# v009_schematics.net
KiCad netlist of a schematic drawn in Altium Designer
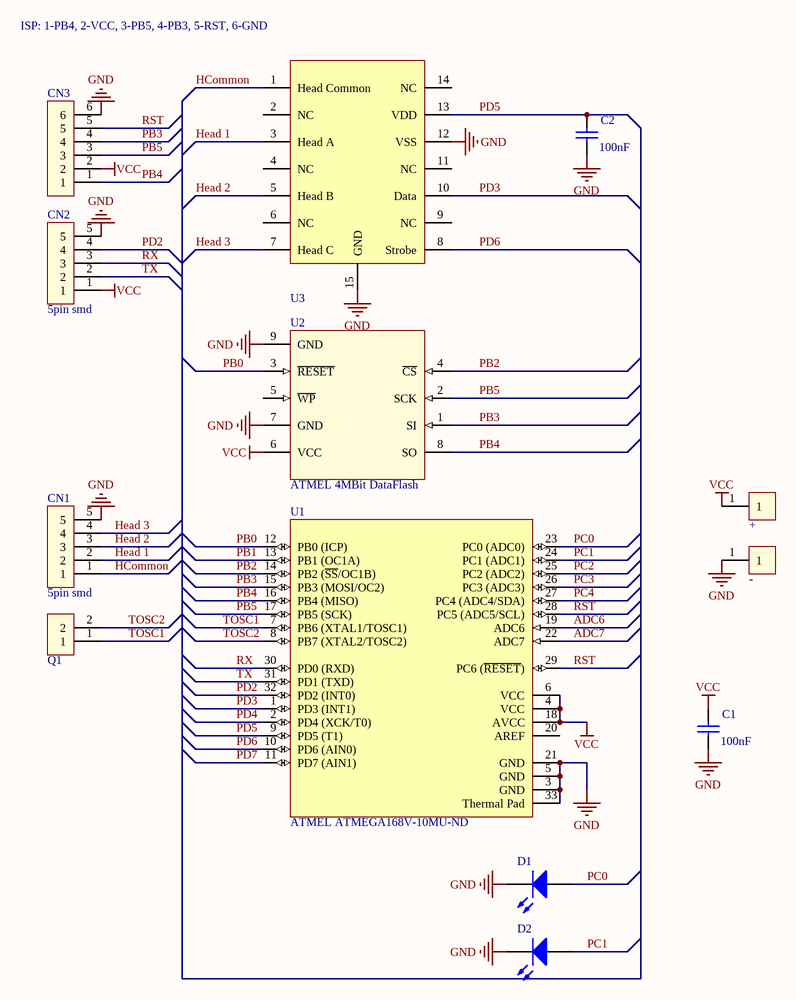
[diagram p0: v009 schematics.SCHDOC]

(export (version "E")
  (design (tool "Eeschema 10.0.6"))
  (components
    (comp (ref "+")
      (value "No component mounted")
      (footprint "SU01LS")
      (libsource (lib "*") (part "1pin smd"))
    )
    (comp (ref "-")
      (value "No component mounted")
      (footprint "SU01LS")
      (libsource (lib "*") (part "1pin smd"))
    )
    (comp (ref "C1")
      (value "100nF")
      (footprint "CC0603(0201)")
      (description "100nf Capacitor - Footprint CC0603 (0201)")
      (fields
        (field (name "DIGI-KEY PART NUMBER") "490-3167-1-ND")
        (field (name "MANUFACTURER") "Murata Electronics")
        (field (name "PUBLISHER") "Altium Limited")
      )
      (libsource (lib "Miscellaneous Devices") (part "Cap"))
    )
    (comp (ref "C2")
      (value "100nF")
      (footprint "CC0603(0201)")
      (description "CAP CER .1UF 6.3V X5R 0201")
      (fields
        (field (name "DIGI-KEY PART NUMBER") "490-3167-1-ND")
        (field (name "PUBLISHER") "Altium Limited")
      )
      (libsource (lib "Miscellaneous Devices") (part "Cap"))
    )
    (comp (ref "CN1")
      (value "5pin smd")
      (footprint "SU05LSR wide")
      (description "No component mounted")
      (libsource (lib "v4lib") (part "5pin smd"))
    )
    (comp (ref "CN2")
      (value "5pin smd")
      (footprint "SU05LSR wide")
      (description "No component mounted")
      (libsource (lib "v4lib") (part "5pin smd"))
    )
    (comp (ref "CN3")
      (value "No component mounted")
      (footprint "SU06LST FULL")
      (libsource (lib "v4lib") (part "6pin smd"))
    )
    (comp (ref "D1")
      (value "LED1")
      (footprint "CC1005(0402)")
      (description "LED 0402 GREEN 465NM TRANSPARENT")
      (fields
        (field (name "DIGI-KEY PART NUMBER") "511-1615-1-ND")
        (field (name "MANUFACTURER") "Rohm Semiconductor")
        (field (name "PUBLISHER") "Altium Limited")
      )
      (libsource (lib "Miscellaneous Devices") (part "LED3"))
    )
    (comp (ref "D2")
      (value "LED1")
      (footprint "CC1005(0402)")
      (description "LED 0402 RED 465NM TRANSPARENT")
      (fields
        (field (name "DIGI-KEY PART NUMBER") "511-1615-1-ND")
        (field (name "MANUFACTURER") "Rohm Semiconductor")
        (field (name "PUBLISHER") "Altium Limited")
      )
      (libsource (lib "Miscellaneous Devices") (part "LED3"))
    )
    (comp (ref "Q1")
      (value "32.768khz crystal 1.5 x 3.2mm")
      (footprint "Quartz SMD (small)")
      (description "CRYSTAL 32.768KHZ 1.5 x 3.2mm")
      (fields
        (field (name "DIGI-KEY PART NUMBER") "535-9542-1-ND")
        (field (name "MANUFACTURER") "Abracon Corporation")
      )
      (libsource (lib "v4lib") (part "2pin smd"))
    )
    (comp (ref "U1")
      (value "ATMEL ATMEGA168V-10MU-ND")
      (footprint "32M1-A L 3")
      (description "ATMEL ATMEGA168V-10MU")
      (fields
        (field (name "DIGI-KEY PART NUMBER") "ATMEGA168V-10MU-ND")
        (field (name "MANUFACTURER") "ATMEL")
        (field (name "PUBLISHER") "Altium Limited")
      )
      (libsource (lib "Atmel Microcontroller 8-Bit AVR") (part "ATmega8L-8MC"))
    )
    (comp (ref "U2")
      (value "ATMEL 4MBit DataFlash")
      (footprint "8m1-a mlf 3")
      (libsource (lib "v4lib") (part "at45db041b"))
    )
    (comp (ref "U3")
      (value "Asic 3V MLF14")
      (footprint "delta asic - 5")
      (fields (field (name "MANUFACTURER") "Magtek") (field (name "MANUFACTURER PART NUMBER") "21006540"))
      (libsource (lib "v4lib") (part "delta asic 3volt"))
    )
  )
  (nets
    (net (code "1") (name "/ADC6") (class "Default")
      (node (ref "U1") (pin "19") (pinfunction "ADC6_19") (pintype "input"))
    )
    (net (code "2") (name "/ADC7") (class "Default")
      (node (ref "U1") (pin "22") (pinfunction "ADC7_22") (pintype "input"))
    )
    (net (code "3") (name "/HCommon") (class "Default")
      (node (ref "CN1") (pin "1") (pinfunction "1_1") (pintype "passive"))
      (node (ref "U3") (pin "1") (pinfunction "Head_Common_1") (pintype "passive"))
    )
    (net (code "4") (name "/Head 1") (class "Default")
      (node (ref "CN1") (pin "2") (pinfunction "2_2") (pintype "passive"))
      (node (ref "U3") (pin "3") (pinfunction "Head_A_3") (pintype "passive"))
    )
    (net (code "5") (name "/Head 2") (class "Default")
      (node (ref "CN1") (pin "3") (pinfunction "3_3") (pintype "passive"))
      (node (ref "U3") (pin "5") (pinfunction "Head_B_5") (pintype "passive"))
    )
    (net (code "6") (name "/Head 3") (class "Default")
      (node (ref "CN1") (pin "4") (pinfunction "4_4") (pintype "passive"))
      (node (ref "U3") (pin "7") (pinfunction "Head_C_7") (pintype "passive"))
    )
    (net (code "7") (name "/PB0") (class "Default")
      (node (ref "U1") (pin "12") (pinfunction "PB0_(ICP)_12") (pintype "bidirectional"))
      (node (ref "U2") (pin "3") (pinfunction "~{RESET}_3") (pintype "input"))
    )
    (net (code "8") (name "/PB1") (class "Default")
      (node (ref "U1") (pin "13") (pinfunction "PB1_(OC1A)_13") (pintype "bidirectional"))
    )
    (net (code "9") (name "/PB2") (class "Default")
      (node (ref "U1") (pin "14") (pinfunction "PB2_(~{SS}/OC1B)_14") (pintype "bidirectional"))
      (node (ref "U2") (pin "4") (pinfunction "~{CS}_4") (pintype "input"))
    )
    (net (code "10") (name "/PB3") (class "Default")
      (node (ref "CN3") (pin "4") (pinfunction "4_4") (pintype "passive"))
      (node (ref "U1") (pin "15") (pinfunction "PB3_(MOSI/OC2)_15") (pintype "bidirectional"))
      (node (ref "U2") (pin "1") (pinfunction "SI_1") (pintype "input"))
    )
    (net (code "11") (name "/PB4") (class "Default")
      (node (ref "CN3") (pin "1") (pinfunction "1_1") (pintype "passive"))
      (node (ref "U1") (pin "16") (pinfunction "PB4_(MISO)_16") (pintype "bidirectional"))
      (node (ref "U2") (pin "8") (pinfunction "SO_8") (pintype "passive"))
    )
    (net (code "12") (name "/PB5") (class "Default")
      (node (ref "CN3") (pin "3") (pinfunction "3_3") (pintype "passive"))
      (node (ref "U1") (pin "17") (pinfunction "PB5_(SCK)_17") (pintype "bidirectional"))
      (node (ref "U2") (pin "2") (pinfunction "SCK_2") (pintype "input"))
    )
    (net (code "13") (name "/PC0") (class "Default")
      (node (ref "D1") (pin "1") (pinfunction "A_1") (pintype "passive"))
      (node (ref "U1") (pin "23") (pinfunction "PC0_(ADC0)_23") (pintype "bidirectional"))
    )
    (net (code "14") (name "/PC1") (class "Default")
      (node (ref "D2") (pin "1") (pinfunction "A_1") (pintype "passive"))
      (node (ref "U1") (pin "24") (pinfunction "PC1_(ADC1)_24") (pintype "bidirectional"))
    )
    (net (code "15") (name "/PC2") (class "Default")
      (node (ref "U1") (pin "25") (pinfunction "PC2_(ADC2)_25") (pintype "bidirectional"))
    )
    (net (code "16") (name "/PC3") (class "Default")
      (node (ref "U1") (pin "26") (pinfunction "PC3_(ADC3)_26") (pintype "bidirectional"))
    )
    (net (code "17") (name "/PC4") (class "Default")
      (node (ref "U1") (pin "27") (pinfunction "PC4_(ADC4/SDA)_27") (pintype "bidirectional"))
    )
    (net (code "18") (name "/PD2") (class "Default")
      (node (ref "CN2") (pin "4") (pinfunction "4_4") (pintype "passive"))
      (node (ref "U1") (pin "32") (pinfunction "PD2_(INT0)_32") (pintype "bidirectional"))
    )
    (net (code "19") (name "/PD3") (class "Default")
      (node (ref "U1") (pin "1") (pinfunction "PD3_(INT1)_1") (pintype "bidirectional"))
      (node (ref "U3") (pin "10") (pinfunction "Data_10") (pintype "passive"))
    )
    (net (code "20") (name "/PD4") (class "Default")
      (node (ref "U1") (pin "2") (pinfunction "PD4_(XCK/T0)_2") (pintype "bidirectional"))
    )
    (net (code "21") (name "/PD5") (class "Default")
      (node (ref "C2") (pin "1") (pinfunction "1_1") (pintype "passive"))
      (node (ref "U1") (pin "9") (pinfunction "PD5_(T1)_9") (pintype "bidirectional"))
      (node (ref "U3") (pin "13") (pinfunction "VDD_13") (pintype "passive"))
    )
    (net (code "22") (name "/PD6") (class "Default")
      (node (ref "U1") (pin "10") (pinfunction "PD6_(AIN0)_10") (pintype "bidirectional"))
      (node (ref "U3") (pin "8") (pinfunction "Strobe_8") (pintype "passive"))
    )
    (net (code "23") (name "/PD7") (class "Default")
      (node (ref "U1") (pin "11") (pinfunction "PD7_(AIN1)_11") (pintype "bidirectional"))
    )
    (net (code "24") (name "/RST") (class "Default")
      (node (ref "CN3") (pin "5") (pinfunction "5_5") (pintype "passive"))
      (node (ref "U1") (pin "28") (pinfunction "PC5_(ADC5/SCL)_28") (pintype "bidirectional"))
      (node (ref "U1") (pin "29") (pinfunction "PC6_(~{RESET})_29") (pintype "bidirectional"))
    )
    (net (code "25") (name "/RX") (class "Default")
      (node (ref "CN2") (pin "3") (pinfunction "3_3") (pintype "passive"))
      (node (ref "U1") (pin "30") (pinfunction "PD0_(RXD)_30") (pintype "bidirectional"))
    )
    (net (code "26") (name "/TOSC1") (class "Default")
      (node (ref "Q1") (pin "1") (pinfunction "1_1") (pintype "passive"))
      (node (ref "U1") (pin "7") (pinfunction "PB6_(XTAL1/TOSC1)_7") (pintype "bidirectional"))
    )
    (net (code "27") (name "/TOSC2") (class "Default")
      (node (ref "Q1") (pin "2") (pinfunction "2_2") (pintype "passive"))
      (node (ref "U1") (pin "8") (pinfunction "PB7_(XTAL2/TOSC2)_8") (pintype "bidirectional"))
    )
    (net (code "28") (name "/TX") (class "Default")
      (node (ref "CN2") (pin "2") (pinfunction "2_2") (pintype "passive"))
      (node (ref "U1") (pin "31") (pinfunction "PD1_(TXD)_31") (pintype "bidirectional"))
    )
    (net (code "29") (name "GND") (class "Default")
      (node (ref "-") (pin "1") (pinfunction "1_1") (pintype "passive"))
      (node (ref "C1") (pin "2") (pinfunction "2_2") (pintype "passive"))
      (node (ref "C2") (pin "2") (pinfunction "2_2") (pintype "passive"))
      (node (ref "CN1") (pin "5") (pinfunction "5_5") (pintype "passive"))
      (node (ref "CN2") (pin "5") (pinfunction "5_5") (pintype "passive"))
      (node (ref "CN3") (pin "6") (pinfunction "6_6") (pintype "passive"))
      (node (ref "D1") (pin "2") (pinfunction "K_2") (pintype "passive"))
      (node (ref "D2") (pin "2") (pinfunction "K_2") (pintype "passive"))
      (node (ref "U1") (pin "21") (pinfunction "GND_21") (pintype "power_in"))
      (node (ref "U1") (pin "3") (pinfunction "GND_3") (pintype "power_in"))
      (node (ref "U1") (pin "33") (pinfunction "Thermal_Pad_33") (pintype "power_in"))
      (node (ref "U1") (pin "5") (pinfunction "GND_5") (pintype "power_in"))
      (node (ref "U2") (pin "7") (pinfunction "GND_7") (pintype "passive"))
      (node (ref "U2") (pin "9") (pinfunction "GND_9") (pintype "power_in"))
      (node (ref "U3") (pin "12") (pinfunction "VSS_12") (pintype "passive"))
      (node (ref "U3") (pin "15") (pinfunction "GND_15") (pintype "passive"))
    )
    (net (code "30") (name "VCC") (class "Default")
      (node (ref "+") (pin "1") (pinfunction "1_1") (pintype "passive"))
      (node (ref "C1") (pin "1") (pinfunction "1_1") (pintype "passive"))
      (node (ref "CN2") (pin "1") (pinfunction "1_1") (pintype "passive"))
      (node (ref "CN3") (pin "2") (pinfunction "2_2") (pintype "passive"))
      (node (ref "U1") (pin "18") (pinfunction "AVCC_18") (pintype "power_in"))
      (node (ref "U1") (pin "4") (pinfunction "VCC_4") (pintype "power_in"))
      (node (ref "U1") (pin "6") (pinfunction "VCC_6") (pintype "power_in"))
      (node (ref "U2") (pin "6") (pinfunction "VCC_6") (pintype "power_in"))
    )
    (net (code "31") (name "unconnected-(U1-AREF-Pad20)") (class "Default")
      (node (ref "U1") (pin "20") (pinfunction "AREF_20") (pintype "passive"))
    )
    (net (code "32") (name "unconnected-(U2-~{WP}-Pad5)") (class "Default")
      (node (ref "U2") (pin "5") (pinfunction "~{WP}_5") (pintype "input"))
    )
    (net (code "33") (name "unconnected-(U3-NC-Pad2)") (class "Default")
      (node (ref "U3") (pin "2") (pinfunction "NC_2") (pintype "passive"))
    )
    (net (code "34") (name "unconnected-(U3-NC-Pad4)") (class "Default")
      (node (ref "U3") (pin "4") (pinfunction "NC_4") (pintype "passive"))
    )
    (net (code "35") (name "unconnected-(U3-NC-Pad6)") (class "Default")
      (node (ref "U3") (pin "6") (pinfunction "NC_6") (pintype "passive"))
    )
    (net (code "36") (name "unconnected-(U3-NC-Pad9)") (class "Default")
      (node (ref "U3") (pin "9") (pinfunction "NC_9") (pintype "passive"))
    )
    (net (code "37") (name "unconnected-(U3-NC-Pad11)") (class "Default")
      (node (ref "U3") (pin "11") (pinfunction "NC_11") (pintype "passive"))
    )
    (net (code "38") (name "unconnected-(U3-NC-Pad14)") (class "Default")
      (node (ref "U3") (pin "14") (pinfunction "NC_14") (pintype "passive"))
    )
  )
)
